# SWR_Tandem_Match.net
KiCad netlist of a schematic drawn in Altium Designer
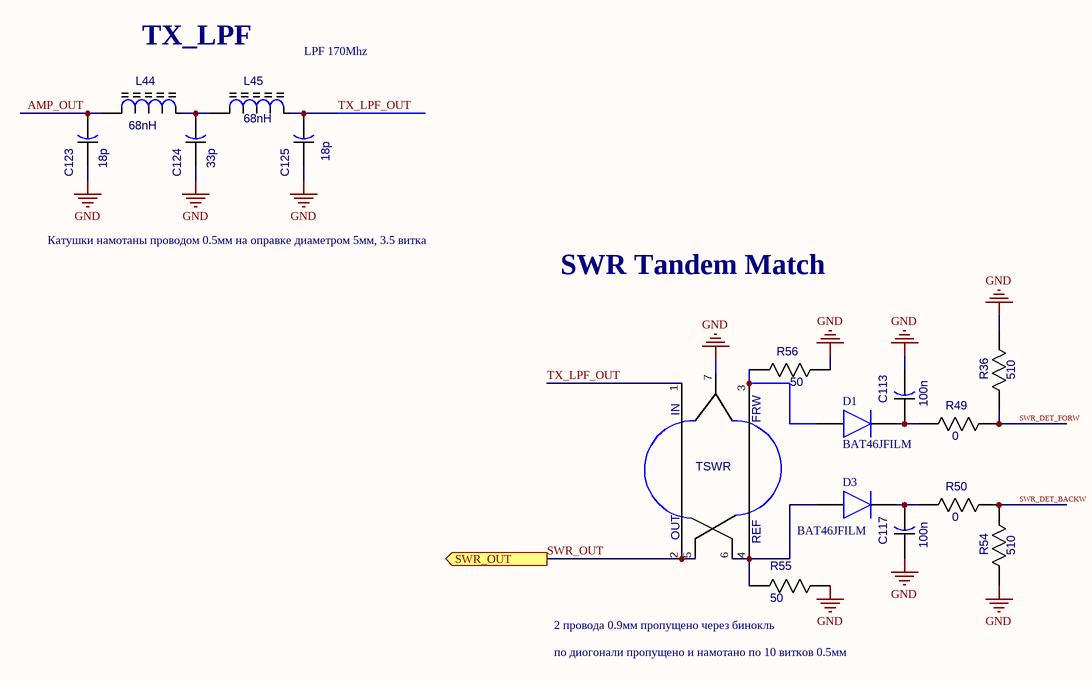
[diagram p0: SWR Tandem Match.SchDoc]

(export (version "E")
  (design (tool "Eeschema 10.0.6"))
  (components
    (comp (ref "C113")
      (value "100n")
      (footprint "CAP_0805")
      (description "CAP_0805")
      (libsource (lib "*") (part "CAP_0805"))
    )
    (comp (ref "C117")
      (value "100n")
      (footprint "CAP_0805")
      (description "CAP_0805")
      (libsource (lib "*") (part "CAP_0805"))
    )
    (comp (ref "C123")
      (value "18p")
      (footprint "CAP_1206")
      (description "CAP_1206")
      (libsource (lib "*") (part "CAP_1206"))
    )
    (comp (ref "C124")
      (value "33p")
      (footprint "CAP_1206")
      (description "CAP_1206")
      (libsource (lib "*") (part "CAP_1206"))
    )
    (comp (ref "C125")
      (value "18p")
      (footprint "CAP_1206")
      (description "CAP_1206")
      (libsource (lib "*") (part "CAP_1206"))
    )
    (comp (ref "D1")
      (value "BAT46JFILM")
      (footprint "SamacSys:SOD2513X117N")
      (description "Diode")
      (fields (field (name "MOUSER PART NUMBER") "511-BAT46JFILM") (field (name "RS PART NUMBER") "7146847P"))
      (libsource (lib "*") (part "BAT46JFILM"))
    )
    (comp (ref "D3")
      (value "BAT46JFILM")
      (footprint "SamacSys:SOD2513X117N")
      (description "Diode")
      (fields (field (name "MOUSER PART NUMBER") "511-BAT46JFILM") (field (name "RS PART NUMBER") "7146847P"))
      (libsource (lib "*") (part "BAT46JFILM"))
    )
    (comp (ref "L44")
      (value "68nH")
      (footprint "IND_FERRITE_CORE_1")
      (description "Inductor")
      (libsource (lib "*") (part "IND_FERRITE_CORE"))
    )
    (comp (ref "L45")
      (value "68nH")
      (footprint "IND_FERRITE_CORE_1")
      (description "Inductor")
      (libsource (lib "*") (part "IND_FERRITE_CORE"))
    )
    (comp (ref "R36")
      (value "510")
      (footprint "RES_0805")
      (description "RES_0805")
      (libsource (lib "*") (part "RES_0805"))
    )
    (comp (ref "R49")
      (value "0")
      (footprint "RES_0805")
      (description "RES_0805")
      (libsource (lib "*") (part "RES_0805"))
    )
    (comp (ref "R50")
      (value "0")
      (footprint "RES_0805")
      (description "RES_0805")
      (libsource (lib "*") (part "RES_0805"))
    )
    (comp (ref "R54")
      (value "510")
      (footprint "RES_0805")
      (description "RES_0805")
      (libsource (lib "*") (part "RES_0805"))
    )
    (comp (ref "R55")
      (value "50")
      (footprint "RES_1206")
      (description "RES_1206")
      (libsource (lib "*") (part "RES_1206"))
    )
    (comp (ref "R56")
      (value "50")
      (footprint "RES_1206")
      (description "RES_1206")
      (libsource (lib "*") (part "RES_1206"))
    )
    (comp (ref "TSWR")
      (value "SWR_TANDEM_MATCH")
      (footprint "SWR_TANDEM_MATCH")
      (libsource (lib "*") (part "SWR_TANDEM_MATCH"))
    )
  )
  (nets
    (net (code "1") (name "/AMP_OUT") (class "Default")
      (node (ref "C123") (pin "2") (pinfunction "2_2") (pintype "passive"))
      (node (ref "L44") (pin "1") (pinfunction "A_1") (pintype "passive"))
    )
    (net (code "2") (name "/SWR_DET_BACKW") (class "Default")
      (node (ref "R50") (pin "2") (pinfunction "2_2") (pintype "passive"))
      (node (ref "R54") (pin "2") (pinfunction "2_2") (pintype "passive"))
    )
    (net (code "3") (name "/SWR_DET_FORW") (class "Default")
      (node (ref "R36") (pin "1") (pinfunction "1_1") (pintype "passive"))
      (node (ref "R49") (pin "2") (pinfunction "2_2") (pintype "passive"))
    )
    (net (code "4") (name "/SWR_OUT") (class "Default")
      (node (ref "TSWR") (pin "2") (pinfunction "2_2") (pintype "passive"))
      (node (ref "TSWR") (pin "5") (pinfunction "5_5") (pintype "passive"))
    )
    (net (code "5") (name "/TX_LPF_OUT") (class "Default")
      (node (ref "C125") (pin "2") (pinfunction "2_2") (pintype "passive"))
      (node (ref "L45") (pin "2") (pinfunction "B_2") (pintype "passive"))
      (node (ref "TSWR") (pin "1") (pinfunction "1_1") (pintype "passive"))
    )
    (net (code "6") (name "GND") (class "Default")
      (node (ref "C113") (pin "2") (pinfunction "2_2") (pintype "passive"))
      (node (ref "C117") (pin "1") (pinfunction "1_1") (pintype "passive"))
      (node (ref "C123") (pin "1") (pinfunction "1_1") (pintype "passive"))
      (node (ref "C124") (pin "1") (pinfunction "1_1") (pintype "passive"))
      (node (ref "C125") (pin "1") (pinfunction "1_1") (pintype "passive"))
      (node (ref "R36") (pin "2") (pinfunction "2_2") (pintype "passive"))
      (node (ref "R54") (pin "1") (pinfunction "1_1") (pintype "passive"))
      (node (ref "R55") (pin "2") (pinfunction "2_2") (pintype "passive"))
      (node (ref "R56") (pin "2") (pinfunction "2_2") (pintype "passive"))
      (node (ref "TSWR") (pin "7") (pinfunction "7_7") (pintype "passive"))
    )
    (net (code "7") (name "Net-(D1-A)") (class "Default")
      (node (ref "D1") (pin "2") (pinfunction "A_2") (pintype "passive"))
      (node (ref "R56") (pin "1") (pinfunction "1_1") (pintype "passive"))
      (node (ref "TSWR") (pin "3") (pinfunction "3_3") (pintype "passive"))
    )
    (net (code "8") (name "Net-(D1-K)") (class "Default")
      (node (ref "C113") (pin "1") (pinfunction "1_1") (pintype "passive"))
      (node (ref "D1") (pin "1") (pinfunction "K_1") (pintype "passive"))
      (node (ref "R49") (pin "1") (pinfunction "1_1") (pintype "passive"))
    )
    (net (code "9") (name "Net-(D3-A)") (class "Default")
      (node (ref "D3") (pin "2") (pinfunction "A_2") (pintype "passive"))
      (node (ref "R55") (pin "1") (pinfunction "1_1") (pintype "passive"))
      (node (ref "TSWR") (pin "4") (pinfunction "4_4") (pintype "passive"))
      (node (ref "TSWR") (pin "6") (pinfunction "6_6") (pintype "passive"))
    )
    (net (code "10") (name "Net-(D3-K)") (class "Default")
      (node (ref "C117") (pin "2") (pinfunction "2_2") (pintype "passive"))
      (node (ref "D3") (pin "1") (pinfunction "K_1") (pintype "passive"))
      (node (ref "R50") (pin "1") (pinfunction "1_1") (pintype "passive"))
    )
    (net (code "11") (name "Net-(L44-B)") (class "Default")
      (node (ref "C124") (pin "2") (pinfunction "2_2") (pintype "passive"))
      (node (ref "L44") (pin "2") (pinfunction "B_2") (pintype "passive"))
      (node (ref "L45") (pin "1") (pinfunction "A_1") (pintype "passive"))
    )
  )
)
